# 140712_AriloTX_REV2_1_0.net
KiCad netlist of a schematic drawn in EAGLE
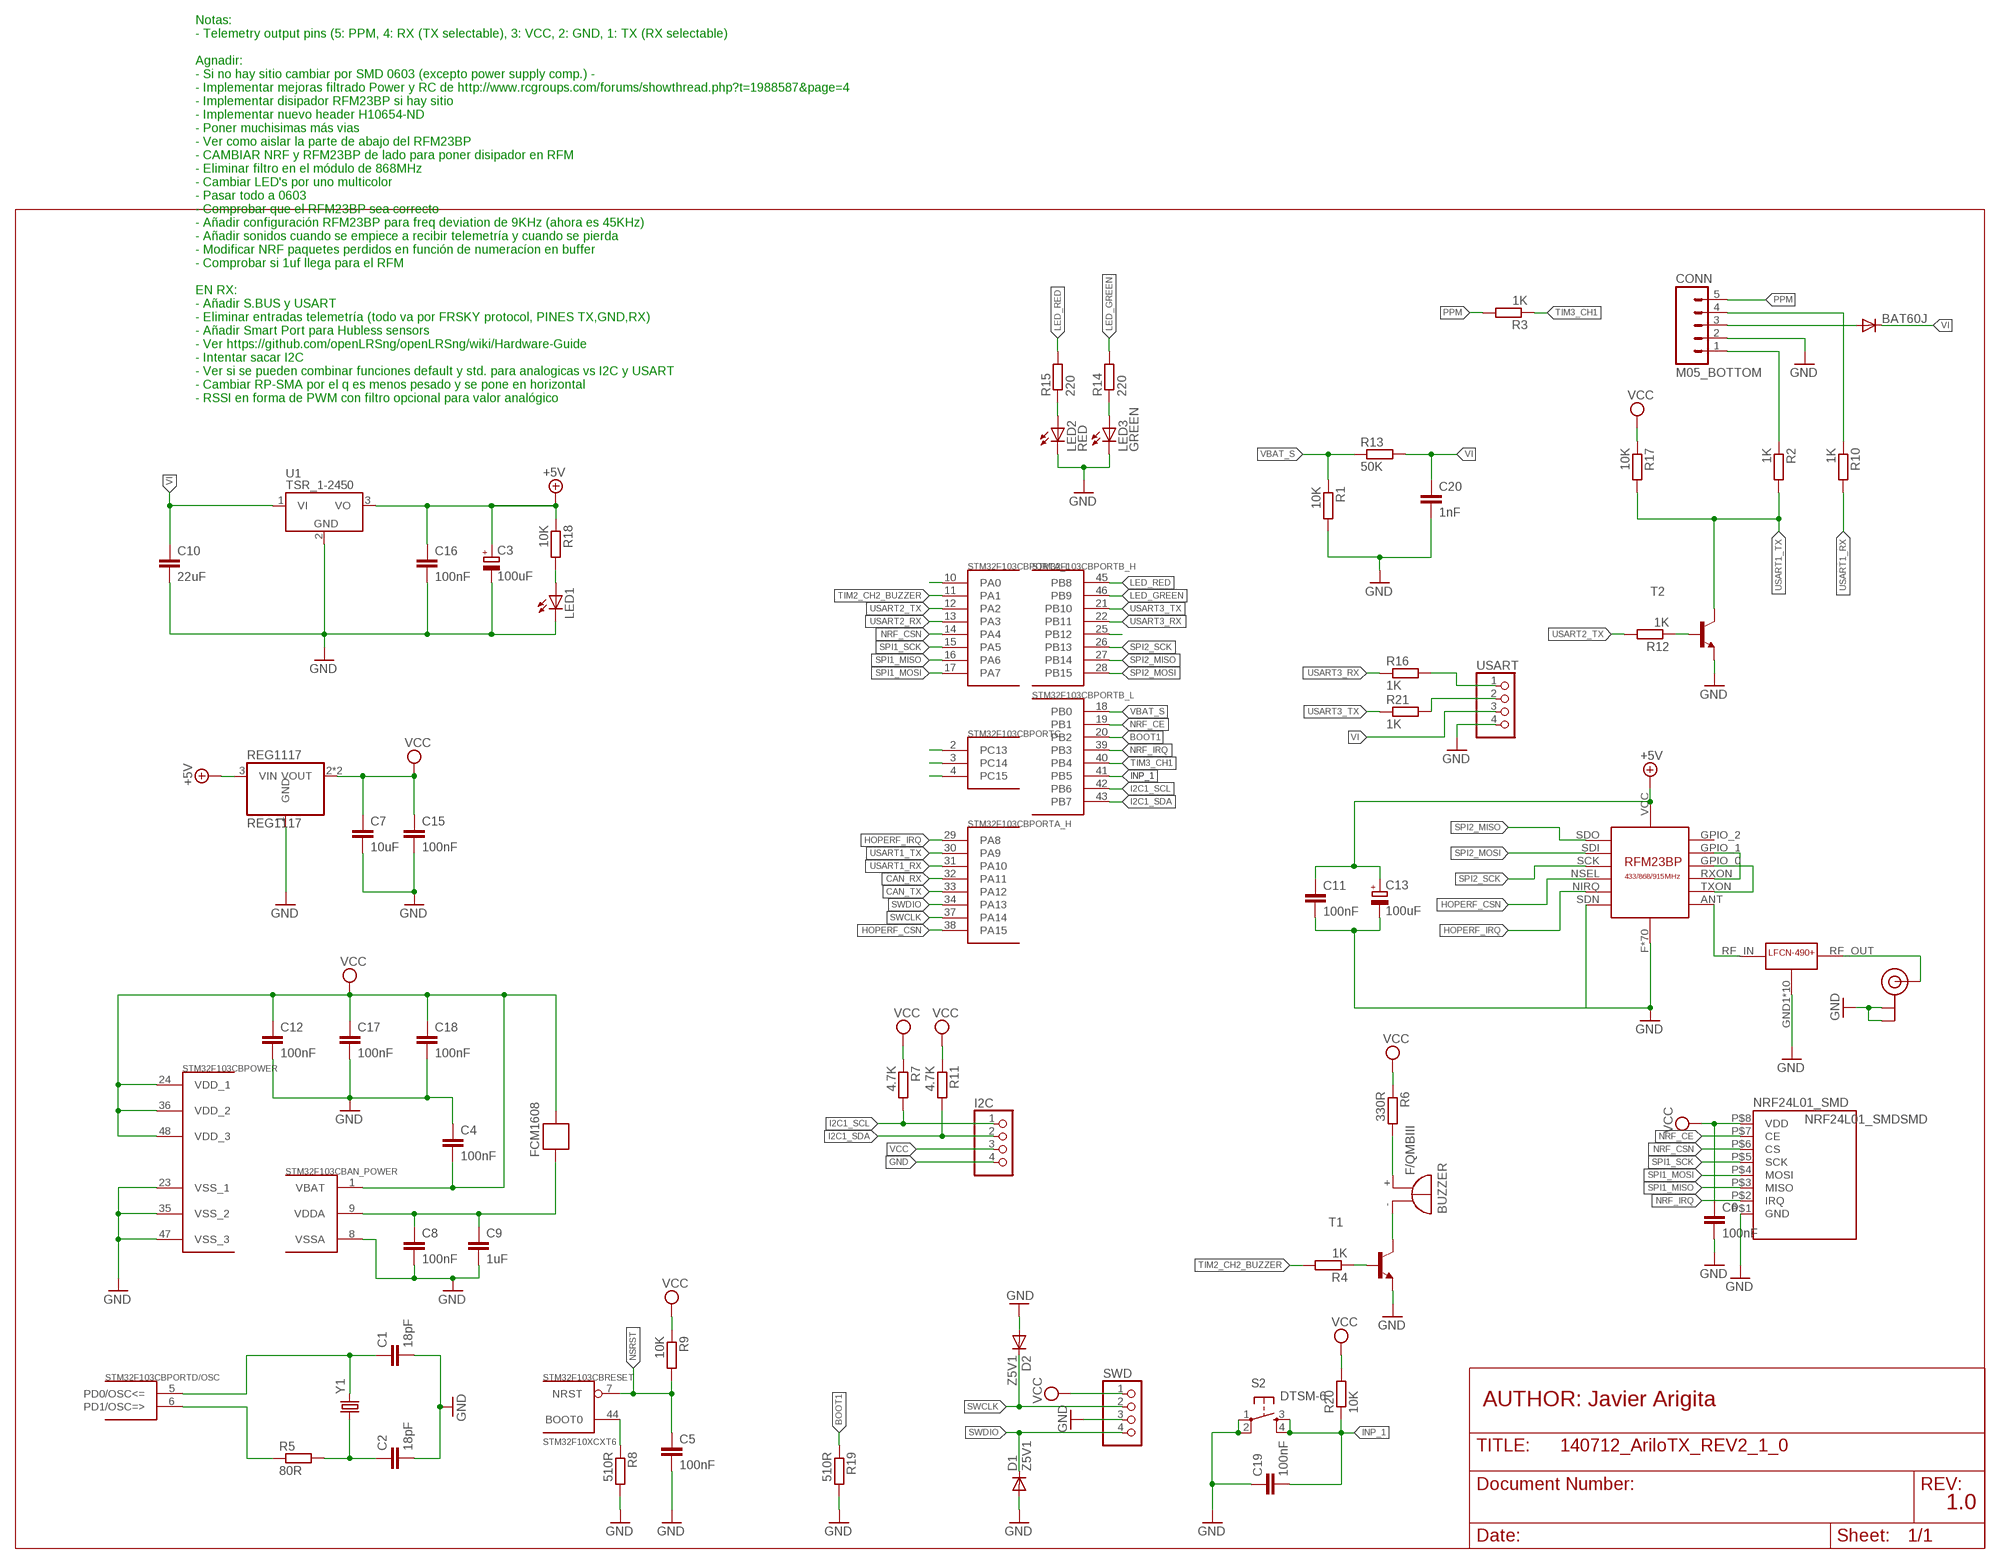
[diagram p0: schematic, sheet 1]

(export (version "E")
  (design (tool "Eeschema 10.0.6"))
  (components
    (comp (ref "BAT60J")
      (value "DIODE-SOD323-R")
      (footprint "eagle-import:SOD323-R")
      (libsource (lib "eagle-import") (part "DIODE-SOD323-R"))
    )
    (comp (ref "BUZZER")
      (value "F/QMBIII")
      (footprint "eagle-import:F_QMBIII")
      (libsource (lib "eagle-import") (part "F/QMBIII"))
    )
    (comp (ref "C1")
      (value "18pF")
      (footprint "eagle-import:C0603")
      (libsource (lib "eagle-import") (part "C-EUC0603"))
    )
    (comp (ref "C2")
      (value "18pF")
      (footprint "eagle-import:C0603")
      (libsource (lib "eagle-import") (part "C-EUC0603"))
    )
    (comp (ref "C3")
      (value "100uF")
      (footprint "eagle-import:SMC_B")
      (libsource (lib "eagle-import") (part "CPOL-EUSMCB"))
    )
    (comp (ref "C4")
      (value "100nF")
      (footprint "eagle-import:C0603")
      (libsource (lib "eagle-import") (part "C-EUC0603"))
    )
    (comp (ref "C5")
      (value "100nF")
      (footprint "eagle-import:C0603")
      (libsource (lib "eagle-import") (part "C-EUC0603"))
    )
    (comp (ref "C6")
      (value "100nF")
      (footprint "eagle-import:C0603")
      (libsource (lib "eagle-import") (part "C-EUC0603"))
    )
    (comp (ref "C7")
      (value "10uF")
      (footprint "eagle-import:C0805")
      (libsource (lib "eagle-import") (part "C-EUC0805"))
    )
    (comp (ref "C8")
      (value "100nF")
      (footprint "eagle-import:C0603")
      (libsource (lib "eagle-import") (part "C-EUC0603"))
    )
    (comp (ref "C9")
      (value "1uF")
      (footprint "eagle-import:C0603")
      (libsource (lib "eagle-import") (part "C-EUC0603"))
    )
    (comp (ref "C10")
      (value "22uF")
      (footprint "eagle-import:C3216")
      (libsource (lib "eagle-import") (part "resistor_C-EUC3216"))
    )
    (comp (ref "C11")
      (value "100nF")
      (footprint "eagle-import:C0603")
      (libsource (lib "eagle-import") (part "C-EUC0603"))
    )
    (comp (ref "C12")
      (value "100nF")
      (footprint "eagle-import:C0603")
      (libsource (lib "eagle-import") (part "C-EUC0603"))
    )
    (comp (ref "C13")
      (value "100uF")
      (footprint "eagle-import:SMC_B")
      (libsource (lib "eagle-import") (part "CPOL-EUSMCB"))
    )
    (comp (ref "C15")
      (value "100nF")
      (footprint "eagle-import:C0603")
      (libsource (lib "eagle-import") (part "C-EUC0603"))
    )
    (comp (ref "C16")
      (value "100nF")
      (footprint "eagle-import:C0603")
      (libsource (lib "eagle-import") (part "C-EUC0603"))
    )
    (comp (ref "C17")
      (value "100nF")
      (footprint "eagle-import:C0603")
      (libsource (lib "eagle-import") (part "C-EUC0603"))
    )
    (comp (ref "C18")
      (value "100nF")
      (footprint "eagle-import:C0603")
      (libsource (lib "eagle-import") (part "C-EUC0603"))
    )
    (comp (ref "C19")
      (value "100nF")
      (footprint "eagle-import:C0603")
      (libsource (lib "eagle-import") (part "C-EUC0603"))
    )
    (comp (ref "C20")
      (value "1nF")
      (footprint "eagle-import:C0603")
      (libsource (lib "eagle-import") (part "C-EUC0603"))
    )
    (comp (ref "CONN")
      (value "M05_BOTTOM")
      (footprint "eagle-import:M05_BOTTOM")
      (libsource (lib "eagle-import") (part "M05_BOTTOM"))
    )
    (comp (ref "D1")
      (value "Z5V1")
      (footprint "eagle-import:SOD323-R")
      (libsource (lib "eagle-import") (part "DIODE-SOD323-R"))
    )
    (comp (ref "D2")
      (value "Z5V1")
      (footprint "eagle-import:SOD323-R")
      (libsource (lib "eagle-import") (part "DIODE-SOD323-R"))
    )
    (comp (ref "FCM1608")
      (value "FERRITE-BEAD")
      (footprint "eagle-import:R0603")
      (libsource (lib "eagle-import") (part "FERRITE-BEAD"))
    )
    (comp (ref "I2C")
      (value "PINHD-1X4")
      (footprint "eagle-import:1X04")
      (libsource (lib "eagle-import") (part "PINHD-1X4"))
    )
    (comp (ref "LED1")
      (value "LEDCHIP-LED0603")
      (footprint "eagle-import:CHIP-LED0603")
      (libsource (lib "eagle-import") (part "LEDCHIP-LED0603"))
    )
    (comp (ref "LED2")
      (value "RED")
      (footprint "eagle-import:CHIP-LED0603")
      (libsource (lib "eagle-import") (part "LEDCHIP-LED0603"))
    )
    (comp (ref "LED3")
      (value "GREEN")
      (footprint "eagle-import:CHIP-LED0603")
      (libsource (lib "eagle-import") (part "LEDCHIP-LED0603"))
    )
    (comp (ref "NRF24L01_SMD")
      (value "NRF24L01_SMDSMD")
      (footprint "eagle-import:NRF24L01_SMD")
      (libsource (lib "eagle-import") (part "NRF24L01_SMDSMD"))
    )
    (comp (ref "R1")
      (value "10K")
      (footprint "eagle-import:R0603")
      (libsource (lib "eagle-import") (part "R-EU_R0603"))
    )
    (comp (ref "R2")
      (value "1K")
      (footprint "eagle-import:R0603")
      (libsource (lib "eagle-import") (part "R-EU_R0603"))
    )
    (comp (ref "R3")
      (value "1K")
      (footprint "eagle-import:R0603")
      (libsource (lib "eagle-import") (part "R-EU_R0603"))
    )
    (comp (ref "R4")
      (value "1K")
      (footprint "eagle-import:R0603")
      (libsource (lib "eagle-import") (part "R-EU_R0603"))
    )
    (comp (ref "R5")
      (value "80R")
      (footprint "eagle-import:R0603")
      (libsource (lib "eagle-import") (part "R-EU_R0603"))
    )
    (comp (ref "R6")
      (value "330R")
      (footprint "eagle-import:R0603")
      (libsource (lib "eagle-import") (part "R-EU_R0603"))
    )
    (comp (ref "R7")
      (value "4.7K")
      (footprint "eagle-import:R0603")
      (libsource (lib "eagle-import") (part "R-EU_R0603"))
    )
    (comp (ref "R8")
      (value "510R")
      (footprint "eagle-import:R0603")
      (libsource (lib "eagle-import") (part "R-EU_R0603"))
    )
    (comp (ref "R9")
      (value "10K")
      (footprint "eagle-import:R0603")
      (libsource (lib "eagle-import") (part "R-EU_R0603"))
    )
    (comp (ref "R10")
      (value "1K")
      (footprint "eagle-import:R0603")
      (libsource (lib "eagle-import") (part "R-EU_R0603"))
    )
    (comp (ref "R11")
      (value "4.7K")
      (footprint "eagle-import:R0603")
      (libsource (lib "eagle-import") (part "R-EU_R0603"))
    )
    (comp (ref "R12")
      (value "1K")
      (footprint "eagle-import:R0603")
      (libsource (lib "eagle-import") (part "R-EU_R0603"))
    )
    (comp (ref "R13")
      (value "50K")
      (footprint "eagle-import:R0603")
      (libsource (lib "eagle-import") (part "R-EU_R0603"))
    )
    (comp (ref "R14")
      (value "220")
      (footprint "eagle-import:R0603")
      (libsource (lib "eagle-import") (part "R-EU_R0603"))
    )
    (comp (ref "R15")
      (value "220")
      (footprint "eagle-import:R0603")
      (libsource (lib "eagle-import") (part "R-EU_R0603"))
    )
    (comp (ref "R16")
      (value "1K")
      (footprint "eagle-import:R0603")
      (libsource (lib "eagle-import") (part "R-EU_R0603"))
    )
    (comp (ref "R17")
      (value "10K")
      (footprint "eagle-import:R0603")
      (libsource (lib "eagle-import") (part "R-EU_R0603"))
    )
    (comp (ref "R18")
      (value "10K")
      (footprint "eagle-import:R0603")
      (libsource (lib "eagle-import") (part "R-EU_R0603"))
    )
    (comp (ref "R19")
      (value "510R")
      (footprint "eagle-import:R0603")
      (libsource (lib "eagle-import") (part "R-EU_R0603"))
    )
    (comp (ref "R20")
      (value "10K")
      (footprint "eagle-import:R0603")
      (libsource (lib "eagle-import") (part "R-EU_R0603"))
    )
    (comp (ref "R21")
      (value "1K")
      (footprint "eagle-import:R0603")
      (libsource (lib "eagle-import") (part "R-EU_R0603"))
    )
    (comp (ref "REG1117")
      (value "REG1117")
      (footprint "eagle-import:SOT223")
      (libsource (lib "eagle-import") (part "REG1117"))
    )
    (comp (ref "S2")
      (value "DTSM-6")
      (footprint "eagle-import:DTSM-6")
      (libsource (lib "eagle-import") (part "DTSM-6"))
    )
    (comp (ref "STM32F103CB")
      (value "STM32F10XCXT6")
      (footprint "eagle-import:TQFP48")
      (libsource (lib "eagle-import") (part "STM32F10XCXT6"))
    )
    (comp (ref "SWD")
      (value "PINHD-1X4")
      (footprint "eagle-import:1X04")
      (libsource (lib "eagle-import") (part "PINHD-1X4"))
    )
    (comp (ref "T1")
      (value "BC848-NPN-SOT23-BEC")
      (footprint "eagle-import:SOT23-BEC")
      (libsource (lib "eagle-import") (part "-NPN-SOT23-BECBC848"))
    )
    (comp (ref "T2")
      (value "BC848-NPN-SOT23-BEC")
      (footprint "eagle-import:SOT23-BEC")
      (libsource (lib "eagle-import") (part "-NPN-SOT23-BECBC848"))
    )
    (comp (ref "U$1")
      (value "RFM23BP")
      (footprint "eagle-import:RFM23BP")
      (libsource (lib "eagle-import") (part "RFM23BP"))
    )
    (comp (ref "U$2")
      (value "LFCN490+")
      (footprint "eagle-import:LFCN490+")
      (libsource (lib "eagle-import") (part "LFCN490+"))
    )
    (comp (ref "U$3")
      (value "U.FL")
      (footprint "eagle-import:U.FL")
      (libsource (lib "eagle-import") (part "U.FL"))
    )
    (comp (ref "U1")
      (value "TSR_1-2450")
      (footprint "eagle-import:TSR-1")
      (libsource (lib "eagle-import") (part "TSR_1-2450"))
    )
    (comp (ref "USART")
      (value "PINHD-1X4")
      (footprint "eagle-import:1X04")
      (libsource (lib "eagle-import") (part "PINHD-1X4"))
    )
    (comp (ref "Y1")
      (value "CRYSTAL5X3")
      (footprint "eagle-import:CRYSTAL-SMD-5X3")
      (libsource (lib "eagle-import") (part "CRYSTAL5X3"))
    )
  )
  (nets
    (net (code "1") (name "+5V") (class "Default")
      (node (ref "C11") (pin "1") (pinfunction "1_1") (pintype "passive"))
      (node (ref "C13") (pin "+") (pinfunction "+_+") (pintype "passive"))
      (node (ref "C16") (pin "1") (pinfunction "1_1") (pintype "passive"))
      (node (ref "C3") (pin "+") (pinfunction "+_+") (pintype "passive"))
      (node (ref "R18") (pin "1") (pinfunction "1_1") (pintype "passive"))
      (node (ref "REG1117") (pin "3") (pinfunction "VIN_3") (pintype "input"))
      (node (ref "U$1") (pin "VCC") (pinfunction "VCC_VCC") (pintype "power_in"))
      (node (ref "U1") (pin "3") (pinfunction "VO_3") (pintype "power_in"))
    )
    (net (code "2") (name "BOOT1") (class "Default")
      (node (ref "R19") (pin "1") (pinfunction "1_1") (pintype "passive"))
      (node (ref "STM32F103CB") (pin "20") (pinfunction "PB2_20") (pintype "bidirectional"))
    )
    (net (code "3") (name "CAN_RX") (class "Default")
      (node (ref "STM32F103CB") (pin "32") (pinfunction "PA11_32") (pintype "bidirectional"))
    )
    (net (code "4") (name "CAN_TX") (class "Default")
      (node (ref "STM32F103CB") (pin "33") (pinfunction "PA12_33") (pintype "bidirectional"))
    )
    (net (code "5") (name "GND") (class "Default")
      (node (ref "C1") (pin "2") (pinfunction "2_2") (pintype "passive"))
      (node (ref "C10") (pin "2") (pinfunction "2_2") (pintype "passive"))
      (node (ref "C11") (pin "2") (pinfunction "2_2") (pintype "passive"))
      (node (ref "C12") (pin "2") (pinfunction "2_2") (pintype "passive"))
      (node (ref "C13") (pin "-") (pinfunction "-_-") (pintype "passive"))
      (node (ref "C15") (pin "2") (pinfunction "2_2") (pintype "passive"))
      (node (ref "C16") (pin "2") (pinfunction "2_2") (pintype "passive"))
      (node (ref "C17") (pin "2") (pinfunction "2_2") (pintype "passive"))
      (node (ref "C18") (pin "2") (pinfunction "2_2") (pintype "passive"))
      (node (ref "C19") (pin "1") (pinfunction "1_1") (pintype "passive"))
      (node (ref "C2") (pin "2") (pinfunction "2_2") (pintype "passive"))
      (node (ref "C20") (pin "2") (pinfunction "2_2") (pintype "passive"))
      (node (ref "C3") (pin "-") (pinfunction "-_-") (pintype "passive"))
      (node (ref "C4") (pin "1") (pinfunction "1_1") (pintype "passive"))
      (node (ref "C5") (pin "2") (pinfunction "2_2") (pintype "passive"))
      (node (ref "C6") (pin "2") (pinfunction "2_2") (pintype "passive"))
      (node (ref "C7") (pin "2") (pinfunction "2_2") (pintype "passive"))
      (node (ref "C8") (pin "2") (pinfunction "2_2") (pintype "passive"))
      (node (ref "C9") (pin "2") (pinfunction "2_2") (pintype "passive"))
      (node (ref "CONN") (pin "2") (pinfunction "2_2") (pintype "passive"))
      (node (ref "D1") (pin "A") (pinfunction "A_A") (pintype "passive"))
      (node (ref "D2") (pin "A") (pinfunction "A_A") (pintype "passive"))
      (node (ref "I2C") (pin "4") (pinfunction "4_4") (pintype "passive"))
      (node (ref "LED1") (pin "C") (pinfunction "C_C") (pintype "passive"))
      (node (ref "LED2") (pin "C") (pinfunction "C_C") (pintype "passive"))
      (node (ref "LED3") (pin "C") (pinfunction "C_C") (pintype "passive"))
      (node (ref "NRF24L01_SMD") (pin "P$1") (pinfunction "GND_P$1") (pintype "power_in"))
      (node (ref "R1") (pin "2") (pinfunction "2_2") (pintype "passive"))
      (node (ref "R19") (pin "2") (pinfunction "2_2") (pintype "passive"))
      (node (ref "R8") (pin "2") (pinfunction "2_2") (pintype "passive"))
      (node (ref "REG1117") (pin "1") (pinfunction "GND_1") (pintype "power_in"))
      (node (ref "S2") (pin "1") (pinfunction "1_1") (pintype "passive"))
      (node (ref "S2") (pin "2") (pinfunction "2_2") (pintype "passive"))
      (node (ref "STM32F103CB") (pin "23") (pinfunction "VSS_1_23") (pintype "power_in"))
      (node (ref "STM32F103CB") (pin "35") (pinfunction "VSS_2_35") (pintype "power_in"))
      (node (ref "STM32F103CB") (pin "47") (pinfunction "VSS_3_47") (pintype "power_in"))
      (node (ref "STM32F103CB") (pin "8") (pinfunction "VSSA_8") (pintype "power_in"))
      (node (ref "SWD") (pin "3") (pinfunction "3_3") (pintype "passive"))
      (node (ref "T1") (pin "E") (pinfunction "E_E") (pintype "passive"))
      (node (ref "T2") (pin "E") (pinfunction "E_E") (pintype "passive"))
      (node (ref "U$1") (pin "F") (pinfunction "GND_F") (pintype "power_in"))
      (node (ref "U$1") (pin "F1") (pinfunction "GND_F1") (pintype "power_in"))
      (node (ref "U$1") (pin "F10") (pinfunction "GND_F10") (pintype "power_in"))
      (node (ref "U$1") (pin "F11") (pinfunction "GND_F11") (pintype "power_in"))
      (node (ref "U$1") (pin "F12") (pinfunction "GND_F12") (pintype "power_in"))
      (node (ref "U$1") (pin "F13") (pinfunction "GND_F13") (pintype "power_in"))
      (node (ref "U$1") (pin "F14") (pinfunction "GND_F14") (pintype "power_in"))
      (node (ref "U$1") (pin "F15") (pinfunction "GND_F15") (pintype "power_in"))
      (node (ref "U$1") (pin "F16") (pinfunction "GND_F16") (pintype "power_in"))
      (node (ref "U$1") (pin "F17") (pinfunction "GND_F17") (pintype "power_in"))
      (node (ref "U$1") (pin "F18") (pinfunction "GND_F18") (pintype "power_in"))
      (node (ref "U$1") (pin "F19") (pinfunction "GND_F19") (pintype "power_in"))
      (node (ref "U$1") (pin "F2") (pinfunction "GND_F2") (pintype "power_in"))
      (node (ref "U$1") (pin "F20") (pinfunction "GND_F20") (pintype "power_in"))
      (node (ref "U$1") (pin "F21") (pinfunction "GND_F21") (pintype "power_in"))
      (node (ref "U$1") (pin "F22") (pinfunction "GND_F22") (pintype "power_in"))
      (node (ref "U$1") (pin "F23") (pinfunction "GND_F23") (pintype "power_in"))
      (node (ref "U$1") (pin "F24") (pinfunction "GND_F24") (pintype "power_in"))
      (node (ref "U$1") (pin "F25") (pinfunction "GND_F25") (pintype "power_in"))
      (node (ref "U$1") (pin "F26") (pinfunction "GND_F26") (pintype "power_in"))
      (node (ref "U$1") (pin "F27") (pinfunction "GND_F27") (pintype "power_in"))
      (node (ref "U$1") (pin "F28") (pinfunction "GND_F28") (pintype "power_in"))
      (node (ref "U$1") (pin "F29") (pinfunction "GND_F29") (pintype "power_in"))
      (node (ref "U$1") (pin "F3") (pinfunction "GND_F3") (pintype "power_in"))
      (node (ref "U$1") (pin "F30") (pinfunction "GND_F30") (pintype "power_in"))
      (node (ref "U$1") (pin "F31") (pinfunction "GND_F31") (pintype "power_in"))
      (node (ref "U$1") (pin "F32") (pinfunction "GND_F32") (pintype "power_in"))
      (node (ref "U$1") (pin "F33") (pinfunction "GND_F33") (pintype "power_in"))
      (node (ref "U$1") (pin "F34") (pinfunction "GND_F34") (pintype "power_in"))
      (node (ref "U$1") (pin "F35") (pinfunction "GND_F35") (pintype "power_in"))
      (node (ref "U$1") (pin "F36") (pinfunction "GND_F36") (pintype "power_in"))
      (node (ref "U$1") (pin "F37") (pinfunction "GND_F37") (pintype "power_in"))
      (node (ref "U$1") (pin "F38") (pinfunction "GND_F38") (pintype "power_in"))
      (node (ref "U$1") (pin "F39") (pinfunction "GND_F39") (pintype "power_in"))
      (node (ref "U$1") (pin "F4") (pinfunction "GND_F4") (pintype "power_in"))
      (node (ref "U$1") (pin "F40") (pinfunction "GND_F40") (pintype "power_in"))
      (node (ref "U$1") (pin "F41") (pinfunction "GND_F41") (pintype "power_in"))
      (node (ref "U$1") (pin "F42") (pinfunction "GND_F42") (pintype "power_in"))
      (node (ref "U$1") (pin "F43") (pinfunction "GND_F43") (pintype "power_in"))
      (node (ref "U$1") (pin "F44") (pinfunction "GND_F44") (pintype "power_in"))
      (node (ref "U$1") (pin "F45") (pinfunction "GND_F45") (pintype "power_in"))
      (node (ref "U$1") (pin "F46") (pinfunction "GND_F46") (pintype "power_in"))
      (node (ref "U$1") (pin "F47") (pinfunction "GND_F47") (pintype "power_in"))
      (node (ref "U$1") (pin "F48") (pinfunction "GND_F48") (pintype "power_in"))
      (node (ref "U$1") (pin "F49") (pinfunction "GND_F49") (pintype "power_in"))
      (node (ref "U$1") (pin "F5") (pinfunction "GND_F5") (pintype "power_in"))
      (node (ref "U$1") (pin "F50") (pinfunction "GND_F50") (pintype "power_in"))
      (node (ref "U$1") (pin "F51") (pinfunction "GND_F51") (pintype "power_in"))
      (node (ref "U$1") (pin "F52") (pinfunction "GND_F52") (pintype "power_in"))
      (node (ref "U$1") (pin "F53") (pinfunction "GND_F53") (pintype "power_in"))
      (node (ref "U$1") (pin "F54") (pinfunction "GND_F54") (pintype "power_in"))
      (node (ref "U$1") (pin "F55") (pinfunction "GND_F55") (pintype "power_in"))
      (node (ref "U$1") (pin "F56") (pinfunction "GND_F56") (pintype "power_in"))
      (node (ref "U$1") (pin "F57") (pinfunction "GND_F57") (pintype "power_in"))
      (node (ref "U$1") (pin "F58") (pinfunction "GND_F58") (pintype "power_in"))
      (node (ref "U$1") (pin "F59") (pinfunction "GND_F59") (pintype "power_in"))
      (node (ref "U$1") (pin "F6") (pinfunction "GND_F6") (pintype "power_in"))
      (node (ref "U$1") (pin "F60") (pinfunction "GND_F60") (pintype "power_in"))
      (node (ref "U$1") (pin "F61") (pinfunction "GND_F61") (pintype "power_in"))
      (node (ref "U$1") (pin "F62") (pinfunction "GND_F62") (pintype "power_in"))
      (node (ref "U$1") (pin "F63") (pinfunction "GND_F63") (pintype "power_in"))
      (node (ref "U$1") (pin "F64") (pinfunction "GND_F64") (pintype "power_in"))
      (node (ref "U$1") (pin "F65") (pinfunction "GND_F65") (pintype "power_in"))
      (node (ref "U$1") (pin "F7") (pinfunction "GND_F7") (pintype "power_in"))
      (node (ref "U$1") (pin "F8") (pinfunction "GND_F8") (pintype "power_in"))
      (node (ref "U$1") (pin "F9") (pinfunction "GND_F9") (pintype "power_in"))
      (node (ref "U$1") (pin "GND1") (pinfunction "GND_GND1") (pintype "power_in"))
      (node (ref "U$1") (pin "GND2") (pinfunction "GND_GND2") (pintype "power_in"))
      (node (ref "U$1") (pin "GND3") (pinfunction "GND_GND3") (pintype "power_in"))
      (node (ref "U$1") (pin "GND_HEAT") (pinfunction "GND_GND_HEAT") (pintype "power_in"))
      (node (ref "U$1") (pin "SDN") (pinfunction "SDN_SDN") (pintype "bidirectional"))
      (node (ref "U$2") (pin "GND1") (pinfunction "GND_GND1") (pintype "bidirectional"))
      (node (ref "U$2") (pin "GND10") (pinfunction "GND_GND10") (pintype "bidirectional"))
      (node (ref "U$2") (pin "GND2") (pinfunction "GND_GND2") (pintype "bidirectional"))
      (node (ref "U$2") (pin "GND3") (pinfunction "GND_GND3") (pintype "bidirectional"))
      (node (ref "U$2") (pin "GND4") (pinfunction "GND_GND4") (pintype "bidirectional"))
      (node (ref "U$2") (pin "GND5") (pinfunction "GND_GND5") (pintype "bidirectional"))
      (node (ref "U$2") (pin "GND6") (pinfunction "GND_GND6") (pintype "bidirectional"))
      (node (ref "U$2") (pin "GND7") (pinfunction "GND_GND7") (pintype "bidirectional"))
      (node (ref "U$2") (pin "GND8") (pinfunction "GND_GND8") (pintype "bidirectional"))
      (node (ref "U$2") (pin "GND9") (pinfunction "GND_GND9") (pintype "bidirectional"))
      (node (ref "U$3") (pin "P$1") (pinfunction "GND_P$1") (pintype "bidirectional"))
      (node (ref "U$3") (pin "P$2") (pinfunction "GND_P$2") (pintype "bidirectional"))
      (node (ref "U1") (pin "2") (pinfunction "GND_2") (pintype "power_in"))
      (node (ref "USART") (pin "4") (pinfunction "4_4") (pintype "passive"))
    )
    (net (code "6") (name "HOPERF_CSN") (class "Default")
      (node (ref "STM32F103CB") (pin "38") (pinfunction "PA15_38") (pintype "bidirectional"))
      (node (ref "U$1") (pin "NSEL") (pinfunction "NSEL_NSEL") (pintype "bidirectional"))
    )
    (net (code "7") (name "HOPERF_IRQ") (class "Default")
      (node (ref "STM32F103CB") (pin "29") (pinfunction "PA8_29") (pintype "bidirectional"))
      (node (ref "U$1") (pin "NIRQ") (pinfunction "NIRQ_NIRQ") (pintype "bidirectional"))
    )
    (net (code "8") (name "I2C1_SCL") (class "Default")
      (node (ref "I2C") (pin "1") (pinfunction "1_1") (pintype "passive"))
      (node (ref "R7") (pin "2") (pinfunction "2_2") (pintype "passive"))
      (node (ref "STM32F103CB") (pin "42") (pinfunction "PB6_42") (pintype "bidirectional"))
    )
    (net (code "9") (name "I2C1_SDA") (class "Default")
      (node (ref "I2C") (pin "2") (pinfunction "2_2") (pintype "passive"))
      (node (ref "R11") (pin "2") (pinfunction "2_2") (pintype "passive"))
      (node (ref "STM32F103CB") (pin "43") (pinfunction "PB7_43") (pintype "bidirectional"))
    )
    (net (code "10") (name "INP_1") (class "Default")
      (node (ref "C19") (pin "2") (pinfunction "2_2") (pintype "passive"))
      (node (ref "R20") (pin "1") (pinfunction "1_1") (pintype "passive"))
      (node (ref "S2") (pin "3") (pinfunction "3_3") (pintype "passive"))
      (node (ref "S2") (pin "4") (pinfunction "4_4") (pintype "passive"))
      (node (ref "STM32F103CB") (pin "41") (pinfunction "PB5_41") (pintype "bidirectional"))
    )
    (net (code "11") (name "LED_GREEN") (class "Default")
      (node (ref "R14") (pin "2") (pinfunction "2_2") (pintype "passive"))
      (node (ref "STM32F103CB") (pin "46") (pinfunction "PB9_46") (pintype "bidirectional"))
    )
    (net (code "12") (name "LED_RED") (class "Default")
      (node (ref "R15") (pin "2") (pinfunction "2_2") (pintype "passive"))
      (node (ref "STM32F103CB") (pin "45") (pinfunction "PB8_45") (pintype "bidirectional"))
    )
    (net (code "13") (name "NRF_CE") (class "Default")
      (node (ref "NRF24L01_SMD") (pin "P$7") (pinfunction "CE_P$7") (pintype "input"))
      (node (ref "STM32F103CB") (pin "19") (pinfunction "PB1_19") (pintype "bidirectional"))
    )
    (net (code "14") (name "NRF_CSN") (class "Default")
      (node (ref "NRF24L01_SMD") (pin "P$6") (pinfunction "CS_P$6") (pintype "input"))
      (node (ref "STM32F103CB") (pin "14") (pinfunction "PA4_14") (pintype "bidirectional"))
    )
    (net (code "15") (name "NRF_IRQ") (class "Default")
      (node (ref "NRF24L01_SMD") (pin "P$2") (pinfunction "IRQ_P$2") (pintype "output"))
      (node (ref "STM32F103CB") (pin "39") (pinfunction "PB3_39") (pintype "bidirectional"))
    )
    (net (code "16") (name "NSRST") (class "Default")
      (node (ref "C5") (pin "1") (pinfunction "1_1") (pintype "passive"))
      (node (ref "R9") (pin "2") (pinfunction "2_2") (pintype "passive"))
      (node (ref "STM32F103CB") (pin "7") (pinfunction "NRST_7") (pintype "input"))
    )
    (net (code "17") (name "Net-(BAT60J-PadA)") (class "Default")
      (node (ref "BAT60J") (pin "A") (pinfunction "A_A") (pintype "passive"))
      (node (ref "CONN") (pin "3") (pinfunction "3_3") (pintype "passive"))
    )
    (net (code "18") (name "Net-(BUZZER-+)") (class "Default")
      (node (ref "BUZZER") (pin "-") (pinfunction "+_-") (pintype "passive"))
      (node (ref "T1") (pin "C") (pinfunction "C_C") (pintype "passive"))
    )
    (net (code "19") (name "Net-(BUZZER--)") (class "Default")
      (node (ref "BUZZER") (pin "+") (pinfunction "-_+") (pintype "passive"))
      (node (ref "R6") (pin "2") (pinfunction "2_2") (pintype "passive"))
    )
    (net (code "20") (name "Net-(C2-Pad1)") (class "Default")
      (node (ref "C2") (pin "1") (pinfunction "1_1") (pintype "passive"))
      (node (ref "R5") (pin "2") (pinfunction "2_2") (pintype "passive"))
      (node (ref "Y1") (pin "1") (pinfunction "1_1") (pintype "passive"))
    )
    (net (code "21") (name "Net-(CONN-Pad1)") (class "Default")
      (node (ref "CONN") (pin "1") (pinfunction "1_1") (pintype "passive"))
      (node (ref "R2") (pin "1") (pinfunction "1_1") (pintype "passive"))
    )
    (net (code "22") (name "Net-(CONN-Pad4)") (class "Default")
      (node (ref "CONN") (pin "4") (pinfunction "4_4") (pintype "passive"))
      (node (ref "R10") (pin "1") (pinfunction "1_1") (pintype "passive"))
    )
    (net (code "23") (name "Net-(FCM1608-P$2)") (class "Default")
      (node (ref "C8") (pin "1") (pinfunction "1_1") (pintype "passive"))
      (node (ref "C9") (pin "1") (pinfunction "1_1") (pintype "passive"))
      (node (ref "FCM1608") (pin "2") (pinfunction "P$2_2") (pintype "bidirectional"))
      (node (ref "STM32F103CB") (pin "9") (pinfunction "VDDA_9") (pintype "power_in"))
    )
    (net (code "24") (name "Net-(LED1-PadA)") (class "Default")
      (node (ref "LED1") (pin "A") (pinfunction "A_A") (pintype "passive"))
      (node (ref "R18") (pin "2") (pinfunction "2_2") (pintype "passive"))
    )
    (net (code "25") (name "Net-(LED2-PadA)") (class "Default")
      (node (ref "LED2") (pin "A") (pinfunction "A_A") (pintype "passive"))
      (node (ref "R15") (pin "1") (pinfunction "1_1") (pintype "passive"))
    )
    (net (code "26") (name "Net-(LED3-PadA)") (class "Default")
      (node (ref "LED3") (pin "A") (pinfunction "A_A") (pintype "passive"))
      (node (ref "R14") (pin "1") (pinfunction "1_1") (pintype "passive"))
    )
    (net (code "27") (name "Net-(R4-Pad1)") (class "Default")
      (node (ref "R4") (pin "1") (pinfunction "1_1") (pintype "passive"))
      (node (ref "T1") (pin "B") (pinfunction "B_B") (pintype "passive"))
    )
    (net (code "28") (name "Net-(R12-Pad1)") (class "Default")
      (node (ref "R12") (pin "1") (pinfunction "1_1") (pintype "passive"))
      (node (ref "T2") (pin "B") (pinfunction "B_B") (pintype "passive"))
    )
    (net (code "29") (name "Net-(R16-Pad2)") (class "Default")
      (node (ref "R16") (pin "2") (pinfunction "2_2") (pintype "passive"))
      (node (ref "USART") (pin "1") (pinfunction "1_1") (pintype "passive"))
    )
    (net (code "30") (name "Net-(R21-Pad2)") (class "Default")
      (node (ref "R21") (pin "2") (pinfunction "2_2") (pintype "passive"))
      (node (ref "USART") (pin "2") (pinfunction "2_2") (pintype "passive"))
    )
    (net (code "31") (name "Net-(STM32F103CBG-PD0{slash}OSC<=)") (class "Default")
      (node (ref "C1") (pin "1") (pinfunction "1_1") (pintype "passive"))
      (node (ref "STM32F103CB") (pin "5") (pinfunction "PD0/OSC<=_5") (pintype "bidirectional"))
      (node (ref "Y1") (pin "3") (pinfunction "2_3") (pintype "passive"))
    )
    (net (code "32") (name "Net-(STM32F103CBG-PD1{slash}OSC=>)") (class "Default")
      (node (ref "R5") (pin "1") (pinfunction "1_1") (pintype "passive"))
      (node (ref "STM32F103CB") (pin "6") (pinfunction "PD1/OSC=>_6") (pintype "bidirectional"))
    )
    (net (code "33") (name "Net-(STM32F103CBI-BOOT0)") (class "Default")
      (node (ref "R8") (pin "1") (pinfunction "1_1") (pintype "passive"))
      (node (ref "STM32F103CB") (pin "44") (pinfunction "BOOT0_44") (pintype "input"))
    )
    (net (code "34") (name "Net-(U$1-PadGPIO_0)") (class "Default")
      (node (ref "U$1") (pin "GPIO_0") (pinfunction "GPIO_0_GPIO_0") (pintype "bidirectional"))
      (node (ref "U$1") (pin "TXON") (pinfunction "TXON_TXON") (pintype "bidirectional"))
    )
    (net (code "35") (name "Net-(U$1-PadGPIO_1)") (class "Default")
      (node (ref "U$1") (pin "GPIO_1") (pinfunction "GPIO_1_GPIO_1") (pintype "bidirectional"))
      (node (ref "U$1") (pin "RXON") (pinfunction "RXON_RXON") (pintype "bidirectional"))
    )
    (net (code "36") (name "Net-(U$2-RF_INP)") (class "Default")
      (node (ref "U$1") (pin "ANT") (pinfunction "ANT_ANT") (pintype "bidirectional"))
      (node (ref "U$2") (pin "RF_IN") (pinfunction "RF_INP_RF_IN") (pintype "bidirectional"))
    )
    (net (code "37") (name "Net-(U$2-RF_OUTP)") (class "Default")
      (node (ref "U$2") (pin "RF_OUT") (pinfunction "RF_OUTP_RF_OUT") (pintype "bidirectional"))
      (node (ref "U$3") (pin "P$3") (pinfunction "SIGNAL_P$3") (pintype "bidirectional"))
    )
    (net (code "38") (name "PPM") (class "Default")
      (node (ref "CONN") (pin "5") (pinfunction "5_5") (pintype "passive"))
      (node (ref "R3") (pin "2") (pinfunction "2_2") (pintype "passive"))
    )
    (net (code "39") (name "SPI1_MISO") (class "Default")
      (node (ref "NRF24L01_SMD") (pin "P$3") (pinfunction "MISO_P$3") (pintype "output"))
      (node (ref "STM32F103CB") (pin "16") (pinfunction "PA6_16") (pintype "bidirectional"))
    )
    (net (code "40") (name "SPI1_MOSI") (class "Default")
      (node (ref "NRF24L01_SMD") (pin "P$4") (pinfunction "MOSI_P$4") (pintype "input"))
      (node (ref "STM32F103CB") (pin "17") (pinfunction "PA7_17") (pintype "bidirectional"))
    )
    (net (code "41") (name "SPI1_SCK") (class "Default")
      (node (ref "NRF24L01_SMD") (pin "P$5") (pinfunction "SCK_P$5") (pintype "input"))
      (node (ref "STM32F103CB") (pin "15") (pinfunction "PA5_15") (pintype "bidirectional"))
    )
    (net (code "42") (name "SPI2_MISO") (class "Default")
      (node (ref "STM32F103CB") (pin "27") (pinfunction "PB14_27") (pintype "bidirectional"))
      (node (ref "U$1") (pin "SDO") (pinfunction "SDO_SDO") (pintype "bidirectional"))
    )
    (net (code "43") (name "SPI2_MOSI") (class "Default")
      (node (ref "STM32F103CB") (pin "28") (pinfunction "PB15_28") (pintype "bidirectional"))
      (node (ref "U$1") (pin "SDI") (pinfunction "SDI_SDI") (pintype "bidirectional"))
    )
    (net (code "44") (name "SPI2_SCK") (class "Default")
      (node (ref "STM32F103CB") (pin "26") (pinfunction "PB13_26") (pintype "bidirectional"))
      (node (ref "U$1") (pin "SCK") (pinfunction "SCK_SCK") (pintype "bidirectional"))
    )
    (net (code "45") (name "SWCLK") (class "Default")
      (node (ref "D2") (pin "C") (pinfunction "C_C") (pintype "passive"))
      (node (ref "STM32F103CB") (pin "37") (pinfunction "PA14_37") (pintype "bidirectional"))
      (node (ref "SWD") (pin "2") (pinfunction "2_2") (pintype "passive"))
    )
    (net (code "46") (name "SWDIO") (class "Default")
      (node (ref "D1") (pin "C") (pinfunction "C_C") (pintype "passive"))
      (node (ref "STM32F103CB") (pin "34") (pinfunction "PA13_34") (pintype "bidirectional"))
      (node (ref "SWD") (pin "4") (pinfunction "4_4") (pintype "passive"))
    )
    (net (code "47") (name "TIM2_CH2_BUZZER") (class "Default")
      (node (ref "R4") (pin "2") (pinfunction "2_2") (pintype "passive"))
      (node (ref "STM32F103CB") (pin "11") (pinfunction "PA1_11") (pintype "bidirectional"))
    )
    (net (code "48") (name "TIM3_CH1") (class "Default")
      (node (ref "R3") (pin "1") (pinfunction "1_1") (pintype "passive"))
      (node (ref "STM32F103CB") (pin "40") (pinfunction "PB4_40") (pintype "bidirectional"))
    )
    (net (code "49") (name "USART1_RX") (class "Default")
      (node (ref "R10") (pin "2") (pinfunction "2_2") (pintype "passive"))
      (node (ref "STM32F103CB") (pin "31") (pinfunction "PA10_31") (pintype "bidirectional"))
    )
    (net (code "50") (name "USART1_TX") (class "Default")
      (node (ref "R17") (pin "2") (pinfunction "2_2") (pintype "passive"))
      (node (ref "R2") (pin "2") (pinfunction "2_2") (pintype "passive"))
      (node (ref "STM32F103CB") (pin "30") (pinfunction "PA9_30") (pintype "bidirectional"))
      (node (ref "T2") (pin "C") (pinfunction "C_C") (pintype "passive"))
    )
    (net (code "51") (name "USART2_RX") (class "Default")
      (node (ref "STM32F103CB") (pin "13") (pinfunction "PA3_13") (pintype "bidirectional"))
    )
    (net (code "52") (name "USART2_TX") (class "Default")
      (node (ref "R12") (pin "2") (pinfunction "2_2") (pintype "passive"))
      (node (ref "STM32F103CB") (pin "12") (pinfunction "PA2_12") (pintype "bidirectional"))
    )
    (net (code "53") (name "USART3_RX") (class "Default")
      (node (ref "R16") (pin "1") (pinfunction "1_1") (pintype "passive"))
      (node (ref "STM32F103CB") (pin "22") (pinfunction "PB11_22") (pintype "bidirectional"))
    )
    (net (code "54") (name "USART3_TX") (class "Default")
      (node (ref "R21") (pin "1") (pinfunction "1_1") (pintype "passive"))
      (node (ref "STM32F103CB") (pin "21") (pinfunction "PB10_21") (pintype "bidirectional"))
    )
    (net (code "55") (name "VBAT_S") (class "Default")
      (node (ref "R1") (pin "1") (pinfunction "1_1") (pintype "passive"))
      (node (ref "R13") (pin "1") (pinfunction "1_1") (pintype "passive"))
      (node (ref "STM32F103CB") (pin "18") (pinfunction "PB0_18") (pintype "bidirectional"))
    )
    (net (code "56") (name "VCC") (class "Default")
      (node (ref "C12") (pin "1") (pinfunction "1_1") (pintype "passive"))
      (node (ref "C15") (pin "1") (pinfunction "1_1") (pintype "passive"))
      (node (ref "C17") (pin "1") (pinfunction "1_1") (pintype "passive"))
      (node (ref "C18") (pin "1") (pinfunction "1_1") (pintype "passive"))
      (node (ref "C4") (pin "2") (pinfunction "2_2") (pintype "passive"))
      (node (ref "C6") (pin "1") (pinfunction "1_1") (pintype "passive"))
      (node (ref "C7") (pin "1") (pinfunction "1_1") (pintype "passive"))
      (node (ref "FCM1608") (pin "1") (pinfunction "P$1_1") (pintype "bidirectional"))
      (node (ref "I2C") (pin "3") (pinfunction "3_3") (pintype "passive"))
      (node (ref "NRF24L01_SMD") (pin "P$8") (pinfunction "VDD_P$8") (pintype "bidirectional"))
      (node (ref "R11") (pin "1") (pinfunction "1_1") (pintype "passive"))
      (node (ref "R17") (pin "1") (pinfunction "1_1") (pintype "passive"))
      (node (ref "R20") (pin "2") (pinfunction "2_2") (pintype "passive"))
      (node (ref "R6") (pin "1") (pinfunction "1_1") (pintype "passive"))
      (node (ref "R7") (pin "1") (pinfunction "1_1") (pintype "passive"))
      (node (ref "R9") (pin "1") (pinfunction "1_1") (pintype "passive"))
      (node (ref "REG1117") (pin "2") (pinfunction "VOUT_2") (pintype "power_in"))
      (node (ref "REG1117") (pin "4") (pinfunction "VOUT_4") (pintype "power_in"))
      (node (ref "STM32F103CB") (pin "1") (pinfunction "VBAT_1") (pintype "power_in"))
      (node (ref "STM32F103CB") (pin "24") (pinfunction "VDD_1_24") (pintype "power_in"))
      (node (ref "STM32F103CB") (pin "36") (pinfunction "VDD_2_36") (pintype "power_in"))
      (node (ref "STM32F103CB") (pin "48") (pinfunction "VDD_3_48") (pintype "power_in"))
      (node (ref "SWD") (pin "1") (pinfunction "1_1") (pintype "passive"))
    )
    (net (code "57") (name "VI") (class "Default")
      (node (ref "BAT60J") (pin "C") (pinfunction "C_C") (pintype "passive"))
      (node (ref "C10") (pin "1") (pinfunction "1_1") (pintype "passive"))
      (node (ref "C20") (pin "1") (pinfunction "1_1") (pintype "passive"))
      (node (ref "R13") (pin "2") (pinfunction "2_2") (pintype "passive"))
      (node (ref "U1") (pin "1") (pinfunction "VI_1") (pintype "power_in"))
      (node (ref "USART") (pin "3") (pinfunction "3_3") (pintype "passive"))
    )
    (net (code "58") (name "unconnected-(STM32F103CBC-PA0-Pad10)") (class "Default")
      (node (ref "STM32F103CB") (pin "10") (pinfunction "PA0_10") (pintype "bidirectional"))
    )
    (net (code "59") (name "unconnected-(STM32F103CBD-PB12-Pad25)") (class "Default")
      (node (ref "STM32F103CB") (pin "25") (pinfunction "PB12_25") (pintype "bidirectional"))
    )
    (net (code "60") (name "unconnected-(STM32F103CBF-PC13-Pad2)") (class "Default")
      (node (ref "STM32F103CB") (pin "2") (pinfunction "PC13_2") (pintype "bidirectional"))
    )
    (net (code "61") (name "unconnected-(STM32F103CBF-PC14-Pad3)") (class "Default")
      (node (ref "STM32F103CB") (pin "3") (pinfunction "PC14_3") (pintype "bidirectional"))
    )
    (net (code "62") (name "unconnected-(STM32F103CBF-PC15-Pad4)") (class "Default")
      (node (ref "STM32F103CB") (pin "4") (pinfunction "PC15_4") (pintype "bidirectional"))
    )
    (net (code "63") (name "unconnected-(U$1-PadGPIO_2)") (class "Default")
      (node (ref "U$1") (pin "GPIO_2") (pinfunction "GPIO_2_GPIO_2") (pintype "bidirectional"))
    )
  )
)
